# EagleSchematicv3.net
KiCad netlist of a schematic drawn in EAGLE
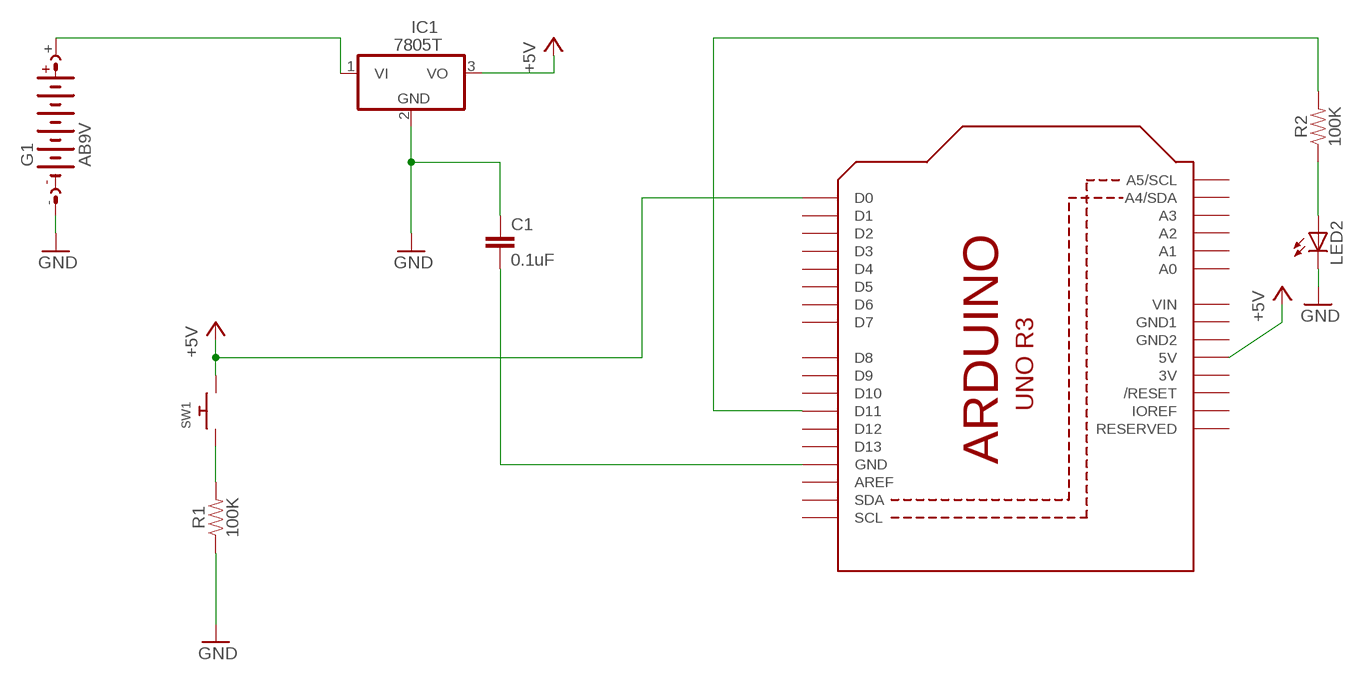
[diagram p0: schematic, sheet 1]

(export (version "E")
  (design (tool "Eeschema 10.0.6"))
  (components
    (comp (ref "C1")
      (value "0.1uF")
      (footprint "eagle-import:0402")
      (libsource (lib "eagle-import") (part "0.1UF-0402-16V-10%"))
    )
    (comp (ref "G1")
      (value "AB9V")
      (footprint "eagle-import:AB9V")
      (libsource (lib "eagle-import") (part "AB9V"))
    )
    (comp (ref "IC1")
      (value "7805T")
      (footprint "eagle-import:TO220H")
      (libsource (lib "eagle-import") (part "78T05"))
    )
    (comp (ref "LED2")
      (value "LED5MM")
      (footprint "eagle-import:LED5MM")
      (libsource (lib "eagle-import") (part "LED5MM"))
    )
    (comp (ref "R1")
      (value "100K")
      (footprint "eagle-import:0402")
      (libsource (lib "eagle-import") (part "100KOHM-0402-1/16W-1%"))
    )
    (comp (ref "R2")
      (value "100K")
      (footprint "eagle-import:0402")
      (libsource (lib "eagle-import") (part "100KOHM-0402-1/16W-1%"))
    )
    (comp (ref "SW1")
      (value "SWITCH_PUSHBUTTONSOFTTOUCHSMD_SJ")
      (footprint "eagle-import:PUSHBUTTON_SMD_SJ")
      (libsource (lib "eagle-import") (part "SWITCH_PUSHBUTTONSOFTTOUCHSMD_SJ"))
    )
    (comp (ref "U1")
      (value "ARDUINOR3-BPLACE")
      (footprint "eagle-import:ARDUINOR3-BPLACE")
      (libsource (lib "eagle-import") (part "ARDUINOR3-BPLACE"))
    )
  )
  (nets
    (net (code "1") (name "+5V") (class "Default")
      (node (ref "IC1") (pin "3") (pinfunction "VO_3") (pintype "passive"))
      (node (ref "SW1") (pin "P$2") (pinfunction "P$2_P$2") (pintype "passive"))
      (node (ref "U1") (pin "5V") (pinfunction "5V_5V") (pintype "power_in"))
      (node (ref "U1") (pin "D0") (pinfunction "D0_D0") (pintype "bidirectional"))
    )
    (net (code "2") (name "/3V") (class "Default")
      (node (ref "U1") (pin "3V") (pinfunction "3V_3V") (pintype "power_in"))
    )
    (net (code "3") (name "/GND1") (class "Default")
      (node (ref "U1") (pin "GND1") (pinfunction "GND1_GND1") (pintype "power_in"))
    )
    (net (code "4") (name "/GND2") (class "Default")
      (node (ref "U1") (pin "GND2") (pinfunction "GND2_GND2") (pintype "power_in"))
    )
    (net (code "5") (name "/VIN") (class "Default")
      (node (ref "U1") (pin "VIN") (pinfunction "VIN_VIN") (pintype "power_in"))
    )
    (net (code "6") (name "GND") (class "Default")
      (node (ref "C1") (pin "1") (pinfunction "1_1") (pintype "passive"))
      (node (ref "G1") (pin "-") (pinfunction "-_-") (pintype "passive"))
      (node (ref "IC1") (pin "2") (pinfunction "GND_2") (pintype "passive"))
      (node (ref "LED2") (pin "K") (pinfunction "C_K") (pintype "passive"))
      (node (ref "R1") (pin "1") (pinfunction "1_1") (pintype "passive"))
    )
    (net (code "7") (name "Net-(C1-Pad2)") (class "Default")
      (node (ref "C1") (pin "2") (pinfunction "2_2") (pintype "passive"))
      (node (ref "U1") (pin "GND") (pinfunction "GND_GND") (pintype "power_in"))
    )
    (net (code "8") (name "Net-(IC1-VI)") (class "Default")
      (node (ref "G1") (pin "+") (pinfunction "+_+") (pintype "passive"))
      (node (ref "IC1") (pin "1") (pinfunction "VI_1") (pintype "input"))
    )
    (net (code "9") (name "Net-(LED2-PadA)") (class "Default")
      (node (ref "LED2") (pin "A") (pinfunction "A_A") (pintype "passive"))
      (node (ref "R2") (pin "1") (pinfunction "1_1") (pintype "passive"))
    )
    (net (code "10") (name "Net-(R1-Pad2)") (class "Default")
      (node (ref "R1") (pin "2") (pinfunction "2_2") (pintype "passive"))
      (node (ref "SW1") (pin "P$1") (pinfunction "P$1_P$1") (pintype "passive"))
    )
    (net (code "11") (name "Net-(R2-Pad2)") (class "Default")
      (node (ref "R2") (pin "2") (pinfunction "2_2") (pintype "passive"))
      (node (ref "U1") (pin "D11") (pinfunction "D11_D11") (pintype "bidirectional"))
    )
    (net (code "12") (name "unconnected-(U1-A4{slash}SDA-PadA4)") (class "Default")
      (node (ref "U1") (pin "A4") (pinfunction "A4/SDA_A4") (pintype "bidirectional"))
    )
    (net (code "13") (name "unconnected-(U1-A5{slash}SCL-PadA5)") (class "Default")
      (node (ref "U1") (pin "A5") (pinfunction "A5/SCL_A5") (pintype "bidirectional"))
    )
    (net (code "14") (name "unconnected-(U1-PadA0)") (class "Default")
      (node (ref "U1") (pin "A0") (pinfunction "A0_A0") (pintype "bidirectional"))
    )
    (net (code "15") (name "unconnected-(U1-PadA1)") (class "Default")
      (node (ref "U1") (pin "A1") (pinfunction "A1_A1") (pintype "bidirectional"))
    )
    (net (code "16") (name "unconnected-(U1-PadA2)") (class "Default")
      (node (ref "U1") (pin "A2") (pinfunction "A2_A2") (pintype "bidirectional"))
    )
    (net (code "17") (name "unconnected-(U1-PadA3)") (class "Default")
      (node (ref "U1") (pin "A3") (pinfunction "A3_A3") (pintype "bidirectional"))
    )
    (net (code "18") (name "unconnected-(U1-PadAREF)") (class "Default")
      (node (ref "U1") (pin "AREF") (pinfunction "AREF_AREF") (pintype "bidirectional"))
    )
    (net (code "19") (name "unconnected-(U1-PadD1)") (class "Default")
      (node (ref "U1") (pin "D1") (pinfunction "D1_D1") (pintype "bidirectional"))
    )
    (net (code "20") (name "unconnected-(U1-PadD2)") (class "Default")
      (node (ref "U1") (pin "D2") (pinfunction "D2_D2") (pintype "bidirectional"))
    )
    (net (code "21") (name "unconnected-(U1-PadD3)") (class "Default")
      (node (ref "U1") (pin "D3") (pinfunction "D3_D3") (pintype "bidirectional"))
    )
    (net (code "22") (name "unconnected-(U1-PadD4)") (class "Default")
      (node (ref "U1") (pin "D4") (pinfunction "D4_D4") (pintype "bidirectional"))
    )
    (net (code "23") (name "unconnected-(U1-PadD5)") (class "Default")
      (node (ref "U1") (pin "D5") (pinfunction "D5_D5") (pintype "bidirectional"))
    )
    (net (code "24") (name "unconnected-(U1-PadD6)") (class "Default")
      (node (ref "U1") (pin "D6") (pinfunction "D6_D6") (pintype "bidirectional"))
    )
    (net (code "25") (name "unconnected-(U1-PadD7)") (class "Default")
      (node (ref "U1") (pin "D7") (pinfunction "D7_D7") (pintype "bidirectional"))
    )
    (net (code "26") (name "unconnected-(U1-PadD8)") (class "Default")
      (node (ref "U1") (pin "D8") (pinfunction "D8_D8") (pintype "bidirectional"))
    )
    (net (code "27") (name "unconnected-(U1-PadD9)") (class "Default")
      (node (ref "U1") (pin "D9") (pinfunction "D9_D9") (pintype "bidirectional"))
    )
    (net (code "28") (name "unconnected-(U1-PadD10)") (class "Default")
      (node (ref "U1") (pin "D10") (pinfunction "D10_D10") (pintype "bidirectional"))
    )
    (net (code "29") (name "unconnected-(U1-PadD12)") (class "Default")
      (node (ref "U1") (pin "D12") (pinfunction "D12_D12") (pintype "bidirectional"))
    )
    (net (code "30") (name "unconnected-(U1-PadD13)") (class "Default")
      (node (ref "U1") (pin "D13") (pinfunction "D13_D13") (pintype "bidirectional"))
    )
    (net (code "31") (name "unconnected-(U1-PadIOREF)") (class "Default")
      (node (ref "U1") (pin "IOREF") (pinfunction "IOREF_IOREF") (pintype "output"))
    )
    (net (code "32") (name "unconnected-(U1-PadRESERVED)") (class "Default")
      (node (ref "U1") (pin "RESERVED") (pinfunction "RESERVED_RESERVED") (pintype "no_connect"))
    )
    (net (code "33") (name "unconnected-(U1-PadSCL)") (class "Default")
      (node (ref "U1") (pin "SCL") (pinfunction "SCL_SCL") (pintype "bidirectional"))
    )
    (net (code "34") (name "unconnected-(U1-PadSDA)") (class "Default")
      (node (ref "U1") (pin "SDA") (pinfunction "SDA_SDA") (pintype "bidirectional"))
    )
    (net (code "35") (name "unconnected-(U1-{slash}RESET-PadRESET)") (class "Default")
      (node (ref "U1") (pin "RESET") (pinfunction "/RESET_RESET") (pintype "bidirectional"))
    )
  )
)
